# hmi.net
KiCad netlist of a schematic drawn in Altium Designer
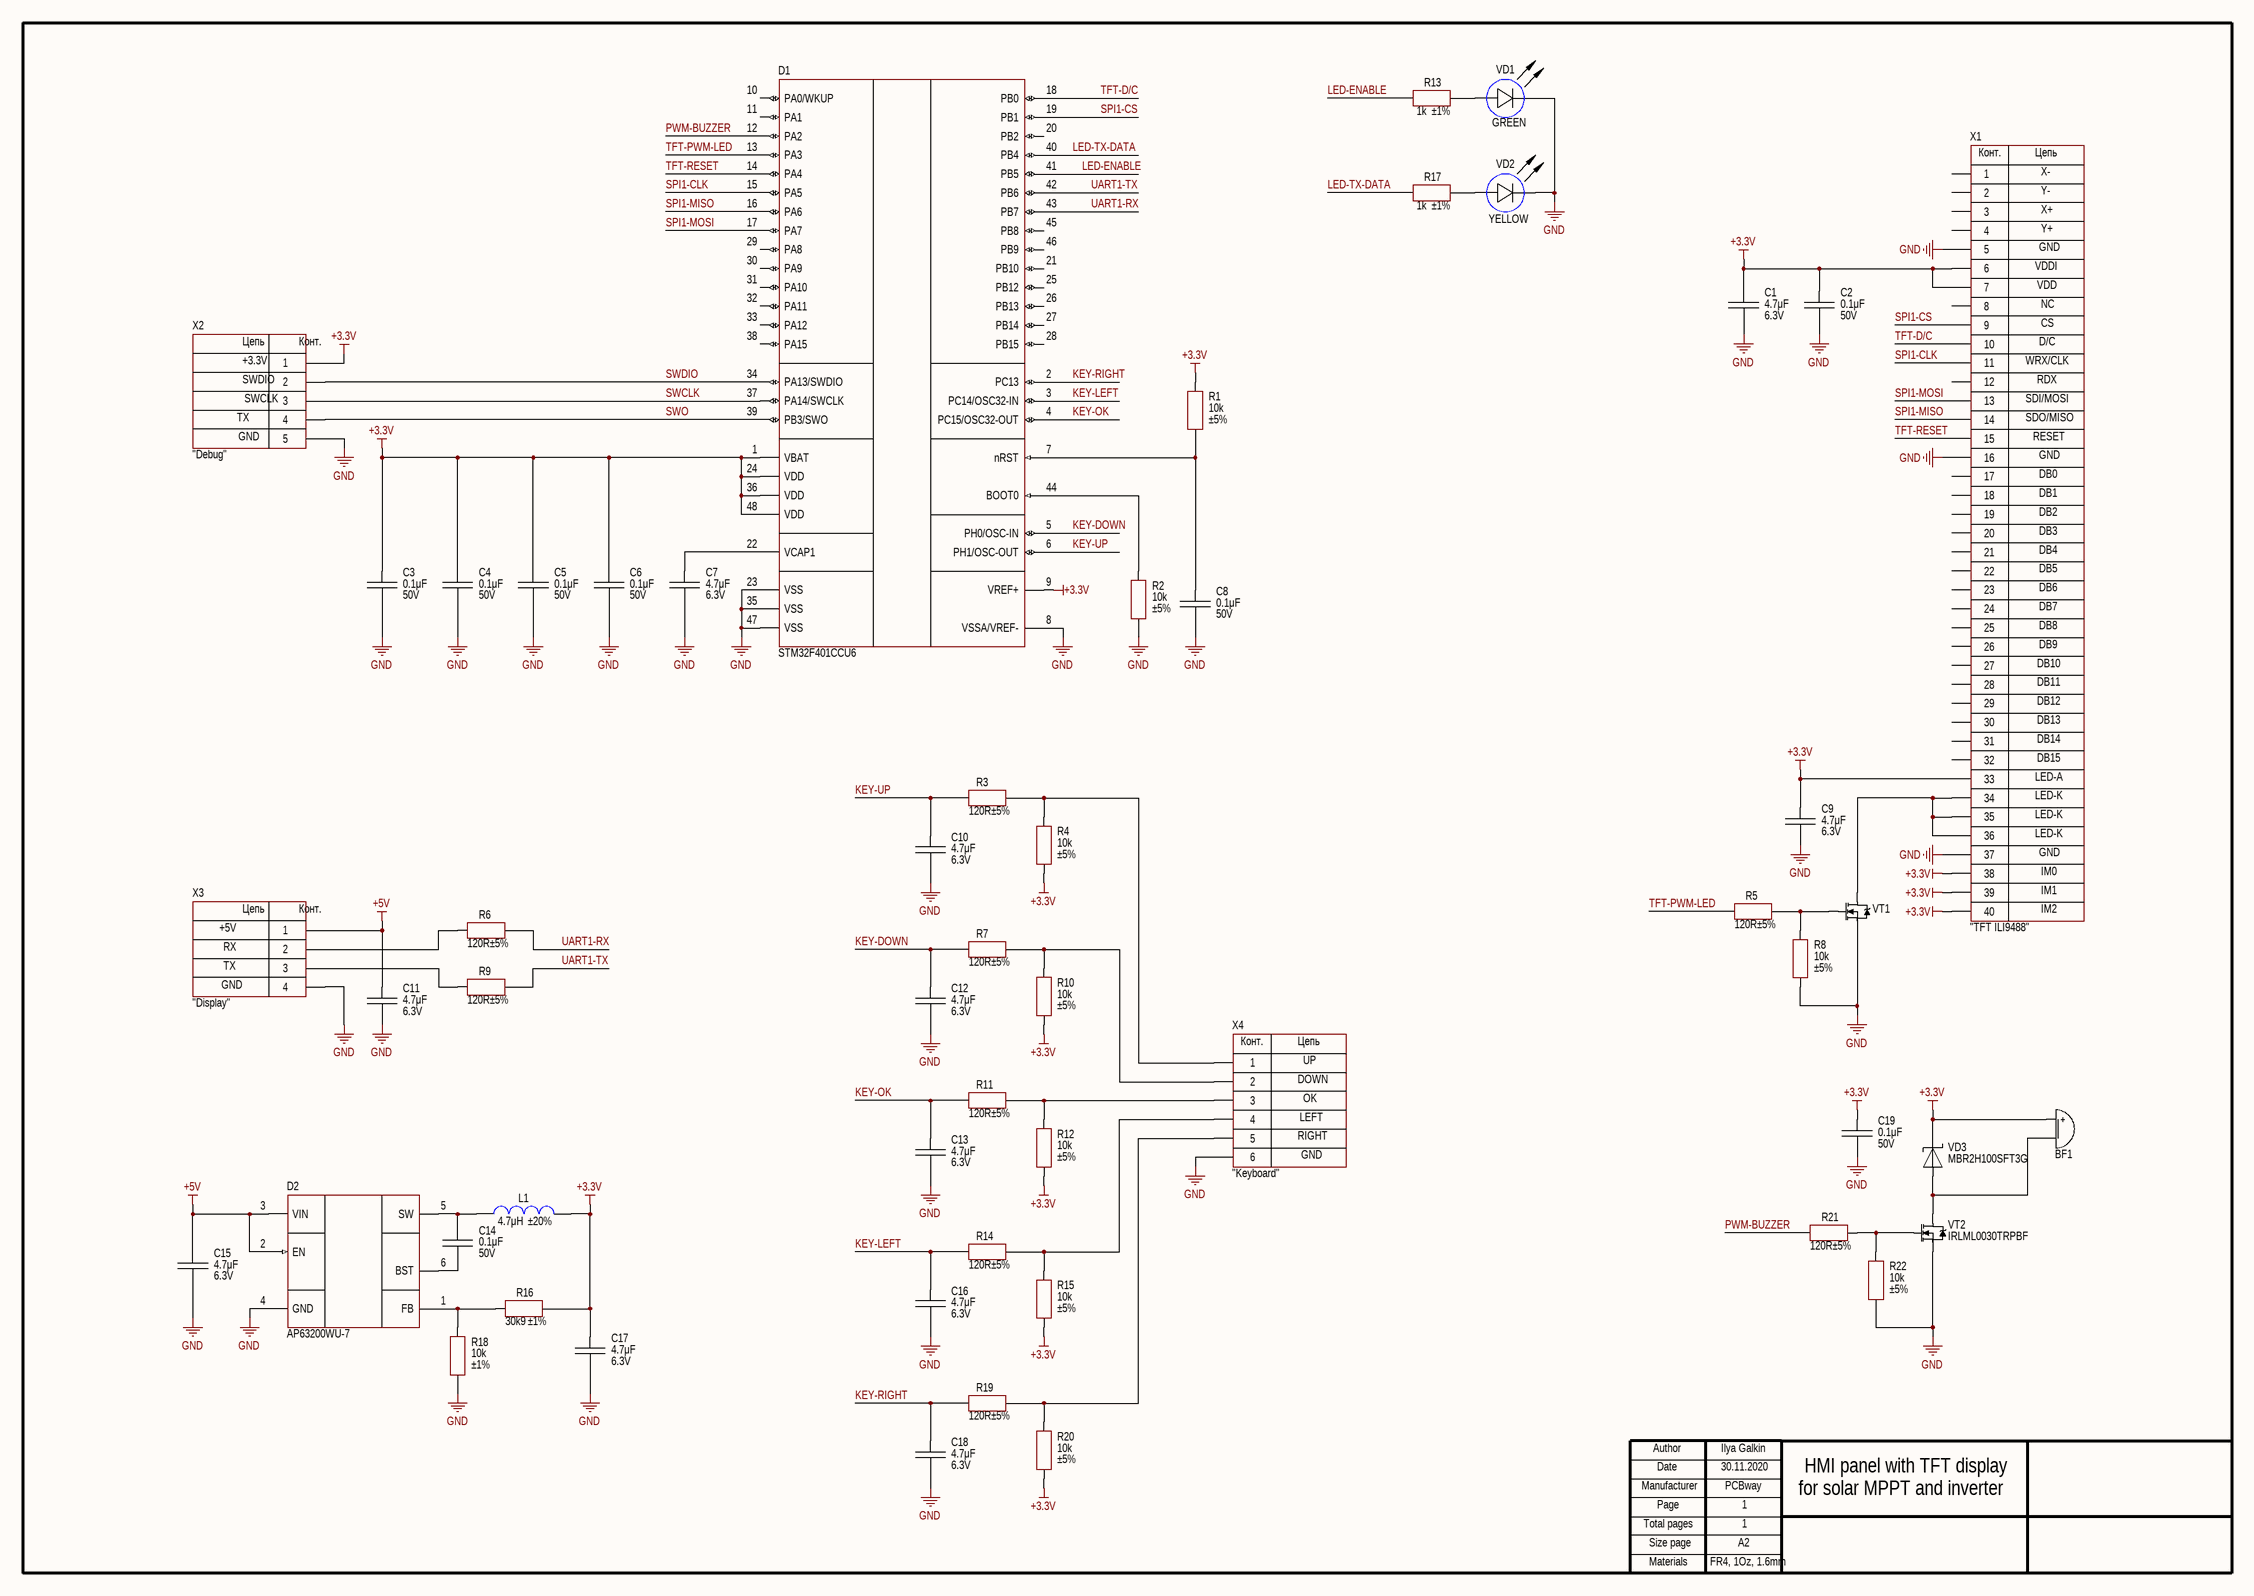
[diagram p0: hmi.SchDoc]

(export (version "E")
  (design (tool "Eeschema 10.0.6"))
  (components
    (comp (ref "BF1")
      (value "~")
      (footprint "BUZ: CMT-7525")
      (fields
        (field (name "MANUFACTURER") "Jiangsu")
        (field (name "VALUEMANUFACTURERPARTNUMBER") "SMD, 7.5x7.5x2.5 mm, 2.7 kHz, 3.6VDC, 80dB, -20...+70°C")
        (field (name "PARTNUMBER") "MLT-7525")
      )
      (libsource (lib "electromechanics") (part "Buzzer"))
    )
    (comp (ref "C1")
      (value "4.7μF")
      (footprint "CAP: 0603")
      (fields
        (field (name "MANUFACTURER") "Samsung")
        (field (name "PARTNUMBER") "CL10B475KQ8NQNC")
        (field (name "VALUEMANUFACTURERPARTNUMBER") "Ceramic capacitor, 4.7μF, X7R, ±10%, 6.3V, 0603, -55...+125°C")
        (field (name "VOLTAGE") "6.3V")
      )
      (libsource (lib "Capacitor") (part "Ceramic_0603"))
    )
    (comp (ref "C2")
      (value "0.1μF")
      (footprint "CAP: 0603")
      (fields
        (field (name "MANUFACTURER") "Samsung")
        (field (name "PARTNUMBER") "CL10B104KB8WPND")
        (field (name "VALUEMANUFACTURERPARTNUMBER") "Ceramic capacitor, 0.1μF, X7R, ±10%, 50V, 0603, -55...+125°C")
        (field (name "VOLTAGE") "50V")
      )
      (libsource (lib "Capacitor") (part "Ceramic_0603"))
    )
    (comp (ref "C3")
      (value "0.1μF")
      (footprint "CAP: 0603")
      (fields
        (field (name "MANUFACTURER") "Samsung")
        (field (name "PARTNUMBER") "CL10B104KB8WPND")
        (field (name "VALUEMANUFACTURERPARTNUMBER") "Ceramic capacitor, 0.1μF, X7R, ±10%, 50V, 0603, -55...+125°C")
        (field (name "VOLTAGE") "50V")
      )
      (libsource (lib "Capacitor") (part "Ceramic_0603"))
    )
    (comp (ref "C4")
      (value "0.1μF")
      (footprint "CAP: 0603")
      (fields
        (field (name "MANUFACTURER") "Samsung")
        (field (name "PARTNUMBER") "CL10B104KB8WPND")
        (field (name "VALUEMANUFACTURERPARTNUMBER") "Ceramic capacitor, 0.1μF, X7R, ±10%, 50V, 0603, -55...+125°C")
        (field (name "VOLTAGE") "50V")
      )
      (libsource (lib "Capacitor") (part "Ceramic_0603"))
    )
    (comp (ref "C5")
      (value "0.1μF")
      (footprint "CAP: 0603")
      (fields
        (field (name "MANUFACTURER") "Samsung")
        (field (name "PARTNUMBER") "CL10B104KB8WPND")
        (field (name "VALUEMANUFACTURERPARTNUMBER") "Ceramic capacitor, 0.1μF, X7R, ±10%, 50V, 0603, -55...+125°C")
        (field (name "VOLTAGE") "50V")
      )
      (libsource (lib "Capacitor") (part "Ceramic_0603"))
    )
    (comp (ref "C6")
      (value "0.1μF")
      (footprint "CAP: 0603")
      (fields
        (field (name "MANUFACTURER") "Samsung")
        (field (name "PARTNUMBER") "CL10B104KB8WPND")
        (field (name "VALUEMANUFACTURERPARTNUMBER") "Ceramic capacitor, 0.1μF, X7R, ±10%, 50V, 0603, -55...+125°C")
        (field (name "VOLTAGE") "50V")
      )
      (libsource (lib "Capacitor") (part "Ceramic_0603"))
    )
    (comp (ref "C7")
      (value "4.7μF")
      (footprint "CAP: 0603")
      (fields
        (field (name "MANUFACTURER") "Samsung")
        (field (name "PARTNUMBER") "CL10B475KQ8NQNC")
        (field (name "VALUEMANUFACTURERPARTNUMBER") "Ceramic capacitor, 4.7μF, X7R, ±10%, 6.3V, 0603, -55...+125°C")
        (field (name "VOLTAGE") "6.3V")
      )
      (libsource (lib "Capacitor") (part "Ceramic_0603"))
    )
    (comp (ref "C8")
      (value "0.1μF")
      (footprint "CAP: 0603")
      (fields
        (field (name "MANUFACTURER") "Samsung")
        (field (name "PARTNUMBER") "CL10B104KB8WPND")
        (field (name "VALUEMANUFACTURERPARTNUMBER") "Ceramic capacitor, 0.1μF, X7R, ±10%, 50V, 0603, -55...+125°C")
        (field (name "VOLTAGE") "50V")
      )
      (libsource (lib "Capacitor") (part "Ceramic_0603"))
    )
    (comp (ref "C9")
      (value "4.7μF")
      (footprint "CAP: 0603")
      (fields
        (field (name "MANUFACTURER") "Samsung")
        (field (name "PARTNUMBER") "CL10B475KQ8NQNC")
        (field (name "VALUEMANUFACTURERPARTNUMBER") "Ceramic capacitor, 4.7μF, X7R, ±10%, 6.3V, 0603, -55...+125°C")
        (field (name "VOLTAGE") "6.3V")
      )
      (libsource (lib "Capacitor") (part "Ceramic_0603"))
    )
    (comp (ref "C10")
      (value "4.7μF")
      (footprint "CAP: 0603")
      (fields
        (field (name "MANUFACTURER") "Samsung")
        (field (name "PARTNUMBER") "CL10B475KQ8NQNC")
        (field (name "VALUEMANUFACTURERPARTNUMBER") "Ceramic capacitor, 4.7μF, X7R, ±10%, 6.3V, 0603, -55...+125°C")
        (field (name "VOLTAGE") "6.3V")
      )
      (libsource (lib "Capacitor") (part "Ceramic_0603"))
    )
    (comp (ref "C11")
      (value "4.7μF")
      (footprint "CAP: 0603")
      (fields
        (field (name "MANUFACTURER") "Samsung")
        (field (name "PARTNUMBER") "CL10B475KQ8NQNC")
        (field (name "VALUEMANUFACTURERPARTNUMBER") "Ceramic capacitor, 4.7μF, X7R, ±10%, 6.3V, 0603, -55...+125°C")
        (field (name "VOLTAGE") "6.3V")
      )
      (libsource (lib "Capacitor") (part "Ceramic_0603"))
    )
    (comp (ref "C12")
      (value "4.7μF")
      (footprint "CAP: 0603")
      (fields
        (field (name "MANUFACTURER") "Samsung")
        (field (name "PARTNUMBER") "CL10B475KQ8NQNC")
        (field (name "VALUEMANUFACTURERPARTNUMBER") "Ceramic capacitor, 4.7μF, X7R, ±10%, 6.3V, 0603, -55...+125°C")
        (field (name "VOLTAGE") "6.3V")
      )
      (libsource (lib "Capacitor") (part "Ceramic_0603"))
    )
    (comp (ref "C13")
      (value "4.7μF")
      (footprint "CAP: 0603")
      (fields
        (field (name "MANUFACTURER") "Samsung")
        (field (name "PARTNUMBER") "CL10B475KQ8NQNC")
        (field (name "VALUEMANUFACTURERPARTNUMBER") "Ceramic capacitor, 4.7μF, X7R, ±10%, 6.3V, 0603, -55...+125°C")
        (field (name "VOLTAGE") "6.3V")
      )
      (libsource (lib "Capacitor") (part "Ceramic_0603"))
    )
    (comp (ref "C14")
      (value "0.1μF")
      (footprint "CAP: 0603")
      (fields
        (field (name "MANUFACTURER") "Samsung")
        (field (name "PARTNUMBER") "CL10B104KB8WPND")
        (field (name "VALUEMANUFACTURERPARTNUMBER") "Ceramic capacitor, 0.1μF, X7R, ±10%, 50V, 0603, -55...+125°C")
        (field (name "VOLTAGE") "50V")
      )
      (libsource (lib "Capacitor") (part "Ceramic_0603"))
    )
    (comp (ref "C15")
      (value "4.7μF")
      (footprint "CAP: 0603")
      (fields
        (field (name "MANUFACTURER") "Samsung")
        (field (name "PARTNUMBER") "CL10B475KQ8NQNC")
        (field (name "VALUEMANUFACTURERPARTNUMBER") "Ceramic capacitor, 4.7μF, X7R, ±10%, 6.3V, 0603, -55...+125°C")
        (field (name "VOLTAGE") "6.3V")
      )
      (libsource (lib "Capacitor") (part "Ceramic_0603"))
    )
    (comp (ref "C16")
      (value "4.7μF")
      (footprint "CAP: 0603")
      (fields
        (field (name "MANUFACTURER") "Samsung")
        (field (name "PARTNUMBER") "CL10B475KQ8NQNC")
        (field (name "VALUEMANUFACTURERPARTNUMBER") "Ceramic capacitor, 4.7μF, X7R, ±10%, 6.3V, 0603, -55...+125°C")
        (field (name "VOLTAGE") "6.3V")
      )
      (libsource (lib "Capacitor") (part "Ceramic_0603"))
    )
    (comp (ref "C17")
      (value "4.7μF")
      (footprint "CAP: 0603")
      (fields
        (field (name "MANUFACTURER") "Samsung")
        (field (name "PARTNUMBER") "CL10B475KQ8NQNC")
        (field (name "VALUEMANUFACTURERPARTNUMBER") "Ceramic capacitor, 4.7μF, X7R, ±10%, 6.3V, 0603, -55...+125°C")
        (field (name "VOLTAGE") "6.3V")
      )
      (libsource (lib "Capacitor") (part "Ceramic_0603"))
    )
    (comp (ref "C18")
      (value "4.7μF")
      (footprint "CAP: 0603")
      (fields
        (field (name "MANUFACTURER") "Samsung")
        (field (name "PARTNUMBER") "CL10B475KQ8NQNC")
        (field (name "VALUEMANUFACTURERPARTNUMBER") "Ceramic capacitor, 4.7μF, X7R, ±10%, 6.3V, 0603, -55...+125°C")
        (field (name "VOLTAGE") "6.3V")
      )
      (libsource (lib "Capacitor") (part "Ceramic_0603"))
    )
    (comp (ref "C19")
      (value "0.1μF")
      (footprint "CAP: 0603")
      (fields
        (field (name "MANUFACTURER") "Samsung")
        (field (name "PARTNUMBER") "CL10B104KB8WPND")
        (field (name "VALUEMANUFACTURERPARTNUMBER") "Ceramic capacitor, 0.1μF, X7R, ±10%, 50V, 0603, -55...+125°C")
        (field (name "VOLTAGE") "50V")
      )
      (libsource (lib "Capacitor") (part "Ceramic_0603"))
    )
    (comp (ref "D1")
      (value "~")
      (footprint "48-QFN (7x7)")
      (description "Cortex-M4")
      (fields (field (name "MANUFACTURER") "STMicroelectronics") (field (name "PARTNUMBER") "STM32F401CCU6"))
      (libsource (lib "ic-mcu") (part "STM32F401CCU6"))
    )
    (comp (ref "D2")
      (value "~")
      (footprint "SOT23-6")
      (description "Buck converter")
      (fields
        (field (name "MANUFACTURER") "Diodes")
        (field (name "VALUEMANUFACTURERPARTNUMBER") "DC/DC buck converter, input 3.8...32V, 500kHz, output 1.2...12V, 2A, -40...+85°C, SOT23-6")
        (field (name "PARTNUMBER") "AP63200WU-7")
      )
      (libsource (lib "ic-power-supply") (part "AP63200WU-7"))
    )
    (comp (ref "L1")
      (value "4.7μH")
      (footprint "IND: CD32")
      (fields
        (field (name "MANUFACTURER") "YJYCOIN")
        (field (name "PARTNUMBER") "CD32YP0302-4R7M")
        (field (name "VALUEMANUFACTURERPARTNUMBER") "Fixed inductor, 4.7μH, ±20%, CD32 series, 1.5A, -40...+125°C")
        (field (name "TOLERANCE") "±20%")
      )
      (libsource (lib "inductor") (part "Inductor_CD32"))
    )
    (comp (ref "R1")
      (value "10k")
      (footprint "RES: 0603")
      (fields
        (field (name "MANUFACTURER") "Yageo")
        (field (name "PARTNUMBER") "RC0603JR-0710KL")
        (field (name "VALUEMANUFACTURERPARTNUMBER") "Resistor film, 10k, ±5%, 0603, 0.1W, -55...+125°C")
        (field (name "TOLERANCE") "±5%")
      )
      (libsource (lib "") (part "Resistor_0603_2"))
    )
    (comp (ref "R2")
      (value "10k")
      (footprint "RES: 0603")
      (fields
        (field (name "MANUFACTURER") "Yageo")
        (field (name "PARTNUMBER") "RC0603JR-0710KL")
        (field (name "VALUEMANUFACTURERPARTNUMBER") "Resistor film, 10k, ±5%, 0603, 0.1W, -55...+125°C")
        (field (name "TOLERANCE") "±5%")
      )
      (libsource (lib "") (part "Resistor_0603_2"))
    )
    (comp (ref "R3")
      (value "120R")
      (footprint "RES: 0603")
      (fields
        (field (name "MANUFACTURER") "Yageo")
        (field (name "PARTNUMBER") "RC0603JR-07120RL")
        (field (name "VALUEMANUFACTURERPARTNUMBER") "Resistor film, 120R, ±5%, 0603, 0.1W, -55...+125°C")
        (field (name "TOLERANCE") "±5%")
      )
      (libsource (lib "resistor") (part "Resistor_0603"))
    )
    (comp (ref "R4")
      (value "10k")
      (footprint "RES: 0603")
      (fields
        (field (name "MANUFACTURER") "Yageo")
        (field (name "PARTNUMBER") "RC0603JR-0710KL")
        (field (name "VALUEMANUFACTURERPARTNUMBER") "Resistor film, 10k, ±5%, 0603, 0.1W, -55...+125°C")
        (field (name "TOLERANCE") "±5%")
      )
      (libsource (lib "") (part "Resistor_0603_2"))
    )
    (comp (ref "R5")
      (value "120R")
      (footprint "RES: 0603")
      (fields
        (field (name "MANUFACTURER") "Yageo")
        (field (name "PARTNUMBER") "RC0603JR-07120RL")
        (field (name "VALUEMANUFACTURERPARTNUMBER") "Resistor film, 120R, ±5%, 0603, 0.1W, -55...+125°C")
        (field (name "TOLERANCE") "±5%")
      )
      (libsource (lib "") (part "Resistor_0603_1"))
    )
    (comp (ref "R6")
      (value "120R")
      (footprint "RES: 0603")
      (fields
        (field (name "MANUFACTURER") "Yageo")
        (field (name "PARTNUMBER") "RC0603JR-07120RL")
        (field (name "VALUEMANUFACTURERPARTNUMBER") "Resistor film, 120R, ±5%, 0603, 0.1W, -55...+125°C")
        (field (name "TOLERANCE") "±5%")
      )
      (libsource (lib "") (part "Resistor_0603_1"))
    )
    (comp (ref "R7")
      (value "120R")
      (footprint "RES: 0603")
      (fields
        (field (name "MANUFACTURER") "Yageo")
        (field (name "PARTNUMBER") "RC0603JR-07120RL")
        (field (name "VALUEMANUFACTURERPARTNUMBER") "Resistor film, 120R, ±5%, 0603, 0.1W, -55...+125°C")
        (field (name "TOLERANCE") "±5%")
      )
      (libsource (lib "resistor") (part "Resistor_0603"))
    )
    (comp (ref "R8")
      (value "10k")
      (footprint "RES: 0603")
      (fields
        (field (name "MANUFACTURER") "Yageo")
        (field (name "PARTNUMBER") "RC0603JR-0710KL")
        (field (name "VALUEMANUFACTURERPARTNUMBER") "Resistor film, 10k, ±5%, 0603, 0.1W, -55...+125°C")
        (field (name "TOLERANCE") "±5%")
      )
      (libsource (lib "") (part "Resistor_0603_2"))
    )
    (comp (ref "R9")
      (value "120R")
      (footprint "RES: 0603")
      (fields
        (field (name "MANUFACTURER") "Yageo")
        (field (name "PARTNUMBER") "RC0603JR-07120RL")
        (field (name "VALUEMANUFACTURERPARTNUMBER") "Resistor film, 120R, ±5%, 0603, 0.1W, -55...+125°C")
        (field (name "TOLERANCE") "±5%")
      )
      (libsource (lib "") (part "Resistor_0603_1"))
    )
    (comp (ref "R10")
      (value "10k")
      (footprint "RES: 0603")
      (fields
        (field (name "MANUFACTURER") "Yageo")
        (field (name "PARTNUMBER") "RC0603JR-0710KL")
        (field (name "VALUEMANUFACTURERPARTNUMBER") "Resistor film, 10k, ±5%, 0603, 0.1W, -55...+125°C")
        (field (name "TOLERANCE") "±5%")
      )
      (libsource (lib "") (part "Resistor_0603_2"))
    )
    (comp (ref "R11")
      (value "120R")
      (footprint "RES: 0603")
      (fields
        (field (name "MANUFACTURER") "Yageo")
        (field (name "PARTNUMBER") "RC0603JR-07120RL")
        (field (name "VALUEMANUFACTURERPARTNUMBER") "Resistor film, 120R, ±5%, 0603, 0.1W, -55...+125°C")
        (field (name "TOLERANCE") "±5%")
      )
      (libsource (lib "resistor") (part "Resistor_0603"))
    )
    (comp (ref "R12")
      (value "10k")
      (footprint "RES: 0603")
      (fields
        (field (name "MANUFACTURER") "Yageo")
        (field (name "PARTNUMBER") "RC0603JR-0710KL")
        (field (name "VALUEMANUFACTURERPARTNUMBER") "Resistor film, 10k, ±5%, 0603, 0.1W, -55...+125°C")
        (field (name "TOLERANCE") "±5%")
      )
      (libsource (lib "") (part "Resistor_0603_2"))
    )
    (comp (ref "R13")
      (value "1k")
      (footprint "RES: 0603")
      (fields
        (field (name "MANUFACTURER") "Yageo")
        (field (name "PARTNUMBER") "RC0603JR-071KL")
        (field (name "VALUEMANUFACTURERPARTNUMBER") "Resistor film, 1k, ±1%, 0603, 0.1W, -55...+125°C")
        (field (name "TOLERANCE") "±1%")
      )
      (libsource (lib "Resistor") (part "Resistor_0603"))
    )
    (comp (ref "R14")
      (value "120R")
      (footprint "RES: 0603")
      (fields
        (field (name "MANUFACTURER") "Yageo")
        (field (name "PARTNUMBER") "RC0603JR-07120RL")
        (field (name "VALUEMANUFACTURERPARTNUMBER") "Resistor film, 120R, ±5%, 0603, 0.1W, -55...+125°C")
        (field (name "TOLERANCE") "±5%")
      )
      (libsource (lib "resistor") (part "Resistor_0603"))
    )
    (comp (ref "R15")
      (value "10k")
      (footprint "RES: 0603")
      (fields
        (field (name "MANUFACTURER") "Yageo")
        (field (name "PARTNUMBER") "RC0603JR-0710KL")
        (field (name "VALUEMANUFACTURERPARTNUMBER") "Resistor film, 10k, ±5%, 0603, 0.1W, -55...+125°C")
        (field (name "TOLERANCE") "±5%")
      )
      (libsource (lib "") (part "Resistor_0603_2"))
    )
    (comp (ref "R16")
      (value "30k9")
      (footprint "RES: 0603")
      (fields
        (field (name "MANUFACTURER") "Yageo")
        (field (name "PARTNUMBER") "RC0603FR-0730K9L")
        (field (name "VALUEMANUFACTURERPARTNUMBER") "Resistor film, 30k9, ±1%, 0603, 0.1W, -55...+125°C")
        (field (name "TOLERANCE") "±1%")
      )
      (libsource (lib "Resistor") (part "Resistor_0603"))
    )
    (comp (ref "R17")
      (value "1k")
      (footprint "RES: 0603")
      (fields
        (field (name "MANUFACTURER") "Yageo")
        (field (name "PARTNUMBER") "RC0603JR-071KL")
        (field (name "VALUEMANUFACTURERPARTNUMBER") "Resistor film, 1k, ±1%, 0603, 0.1W, -55...+125°C")
        (field (name "TOLERANCE") "±1%")
      )
      (libsource (lib "Resistor") (part "Resistor_0603"))
    )
    (comp (ref "R18")
      (value "10k")
      (footprint "RES: 0603")
      (fields
        (field (name "MANUFACTURER") "Yageo")
        (field (name "PARTNUMBER") "AC0603FR-0710KL")
        (field (name "VALUEMANUFACTURERPARTNUMBER") "Resistor film, 10k, ±1%, 0603, 0.1W, -55...+125°C")
        (field (name "TOLERANCE") "±1%")
      )
      (libsource (lib "") (part "Resistor_0603_2"))
    )
    (comp (ref "R19")
      (value "120R")
      (footprint "RES: 0603")
      (fields
        (field (name "MANUFACTURER") "Yageo")
        (field (name "PARTNUMBER") "RC0603JR-07120RL")
        (field (name "VALUEMANUFACTURERPARTNUMBER") "Resistor film, 120R, ±5%, 0603, 0.1W, -55...+125°C")
        (field (name "TOLERANCE") "±5%")
      )
      (libsource (lib "resistor") (part "Resistor_0603"))
    )
    (comp (ref "R20")
      (value "10k")
      (footprint "RES: 0603")
      (fields
        (field (name "MANUFACTURER") "Yageo")
        (field (name "PARTNUMBER") "RC0603JR-0710KL")
        (field (name "VALUEMANUFACTURERPARTNUMBER") "Resistor film, 10k, ±5%, 0603, 0.1W, -55...+125°C")
        (field (name "TOLERANCE") "±5%")
      )
      (libsource (lib "") (part "Resistor_0603_2"))
    )
    (comp (ref "R21")
      (value "120R")
      (footprint "RES: 0603")
      (fields
        (field (name "MANUFACTURER") "Yageo")
        (field (name "PARTNUMBER") "RC0603JR-07120RL")
        (field (name "VALUEMANUFACTURERPARTNUMBER") "Resistor film, 120R, ±5%, 0603, 0.1W, -55...+125°C")
        (field (name "TOLERANCE") "±5%")
      )
      (libsource (lib "") (part "Resistor_0603_1"))
    )
    (comp (ref "R22")
      (value "10k")
      (footprint "RES: 0603")
      (fields
        (field (name "MANUFACTURER") "Yageo")
        (field (name "PARTNUMBER") "RC0603JR-0710KL")
        (field (name "VALUEMANUFACTURERPARTNUMBER") "Resistor film, 10k, ±5%, 0603, 0.1W, -55...+125°C")
        (field (name "TOLERANCE") "±5%")
      )
      (libsource (lib "") (part "Resistor_0603_2"))
    )
    (comp (ref "VD1")
      (value "~")
      (footprint "LED: 0603G")
      (fields
        (field (name "MANUFACTURER") "Wurth")
        (field (name "VALUEMANUFACTURERPARTNUMBER") "LED, 20mA, 2V, 0603, -55...+150°C")
        (field (name "PARTNUMBER") "150060VS75000")
        (field (name "COLOR") "GREEN")
      )
      (libsource (lib "Diode") (part "LED_single"))
    )
    (comp (ref "VD2")
      (value "~")
      (footprint "LED: 0603Y")
      (fields
        (field (name "MANUFACTURER") "Wurth")
        (field (name "VALUEMANUFACTURERPARTNUMBER") "LED, 20mA, 2V, 0603, -55...+150°C")
        (field (name "PARTNUMBER") "150060YS75000")
        (field (name "COLOR") "YELLOW")
      )
      (libsource (lib "Diode") (part "LED_single"))
    )
    (comp (ref "VD3")
      (value "~")
      (footprint "DIODE: SOD123F")
      (fields
        (field (name "MANUFACTURER") "ON Semiconductor")
        (field (name "VALUEMANUFACTURERPARTNUMBER") "Schottky diode, 100V, 2A, 840mV, 15pF, SOD-123F, -55...+150°C")
        (field (name "VOLTAGE") "100V")
        (field (name "PARTNUMBER") "MBR2H100SFT3G")
      )
      (libsource (lib "Diode") (part "Schottky_single"))
    )
    (comp (ref "VT1")
      (value "~")
      (footprint "SOT23")
      (fields
        (field (name "MANUFACTURER") "Infineon Technologies")
        (field (name "VALUEMANUFACTURERPARTNUMBER") "MOSFET N-channel transistor, 30V, 5.3A, 2.6nC, 1.3W, 27mOhm, 382pF, SOT-23, -55...+150°C")
        (field (name "PARTNUMBER") "IRLML0030TRPBF")
      )
      (libsource (lib "transistor") (part "MOSFET_N_132"))
    )
    (comp (ref "VT2")
      (value "~")
      (footprint "SOT23")
      (fields
        (field (name "MANUFACTURER") "Infineon Technologies")
        (field (name "VALUEMANUFACTURERPARTNUMBER") "MOSFET N-channel transistor, 30V, 5.3A, 2.6nC, 1.3W, 27mOhm, 382pF, SOT-23, -55...+150°C")
        (field (name "PARTNUMBER") "IRLML0030TRPBF")
      )
      (libsource (lib "transistor") (part "MOSFET_N_132"))
    )
    (comp (ref "X1")
      (value "~")
      (footprint "CON: FFC/FPC-40-0.5")
      (fields
        (field (name "MANUFACTURER") "JUSHUO")
        (field (name "VALUEMANUFACTURERPARTNUMBER") "Connector, 40pin, 0.5mm, FFC/FPC, Top contact")
        (field (name "PARTNUMBER") "AFC07-S40ECC-00")
        (field (name "COMMENTTEXT") "\"TFT ILI9488\"")
      )
      (libsource (lib "connector") (part "Connector_FFC_40"))
    )
    (comp (ref "X2")
      (value "~")
      (footprint "CON: PLS-5")
      (fields
        (field (name "MANUFACTURER") "Connfly")
        (field (name "VALUEMANUFACTURERPARTNUMBER") "Connector, 5pin, 2.54mm, 500VAC, 3A")
        (field (name "PARTNUMBER") "PLS-5")
        (field (name "COMMENTTEXT") "\"Debug\"")
      )
      (libsource (lib "connector") (part "PLS-5"))
    )
    (comp (ref "X3")
      (value "~")
      (footprint "CON: CWF-4R")
      (fields
        (field (name "MANUFACTURER") "Connfly")
        (field (name "VALUEMANUFACTURERPARTNUMBER") "Connector, 4pin, 2.54mm, 250VAC, 3A")
        (field (name "PARTNUMBER") "CWF-4R")
        (field (name "COMMENTTEXT") "\"Display\"")
      )
      (libsource (lib "connector") (part "CWF-4"))
    )
    (comp (ref "X4")
      (value "~")
      (footprint "CON: CWF-6R")
      (fields
        (field (name "MANUFACTURER") "Connfly")
        (field (name "VALUEMANUFACTURERPARTNUMBER") "Connector, 6pin, 2.54mm, 250VAC, 3A")
        (field (name "PARTNUMBER") "CWF-6R")
        (field (name "COMMENTTEXT") "\"Keyboard\"")
      )
      (libsource (lib "connector") (part "CWF-6"))
    )
  )
  (nets
    (net (code "1") (name "+3.3V") (class "Default")
      (node (ref "BF1") (pin "1") (pinfunction "+_1") (pintype "passive"))
      (node (ref "C1") (pin "2") (pinfunction "2_2") (pintype "power_in"))
      (node (ref "C17") (pin "2") (pinfunction "2_2") (pintype "power_in"))
      (node (ref "C19") (pin "2") (pinfunction "2_2") (pintype "power_in"))
      (node (ref "C2") (pin "2") (pinfunction "2_2") (pintype "power_in"))
      (node (ref "C3") (pin "2") (pinfunction "2_2") (pintype "power_in"))
      (node (ref "C4") (pin "2") (pinfunction "2_2") (pintype "power_in"))
      (node (ref "C5") (pin "2") (pinfunction "2_2") (pintype "power_in"))
      (node (ref "C6") (pin "2") (pinfunction "2_2") (pintype "power_in"))
      (node (ref "C9") (pin "2") (pinfunction "2_2") (pintype "power_in"))
      (node (ref "D1") (pin "1") (pinfunction "VBAT_1") (pintype "passive"))
      (node (ref "D1") (pin "24") (pinfunction "VDD_24") (pintype "passive"))
      (node (ref "D1") (pin "36") (pinfunction "VDD_36") (pintype "passive"))
      (node (ref "D1") (pin "48") (pinfunction "VDD_48") (pintype "passive"))
      (node (ref "D1") (pin "9") (pinfunction "VREF+_9") (pintype "passive"))
      (node (ref "L1") (pin "1") (pinfunction "1_1") (pintype "passive"))
      (node (ref "R1") (pin "2") (pinfunction "2_2") (pintype "passive"))
      (node (ref "R10") (pin "1") (pinfunction "1_1") (pintype "passive"))
      (node (ref "R12") (pin "1") (pinfunction "1_1") (pintype "passive"))
      (node (ref "R15") (pin "1") (pinfunction "1_1") (pintype "passive"))
      (node (ref "R16") (pin "1") (pinfunction "1_1") (pintype "passive"))
      (node (ref "R20") (pin "1") (pinfunction "1_1") (pintype "passive"))
      (node (ref "R4") (pin "1") (pinfunction "1_1") (pintype "passive"))
      (node (ref "VD3") (pin "2") (pinfunction "2_2") (pintype "passive"))
      (node (ref "X1") (pin "33") (pinfunction "33_33") (pintype "passive"))
      (node (ref "X1") (pin "38") (pinfunction "38_38") (pintype "passive"))
      (node (ref "X1") (pin "39") (pinfunction "39_39") (pintype "passive"))
      (node (ref "X1") (pin "40") (pinfunction "40_40") (pintype "passive"))
      (node (ref "X1") (pin "6") (pinfunction "6_6") (pintype "passive"))
      (node (ref "X1") (pin "7") (pinfunction "7_7") (pintype "passive"))
      (node (ref "X2") (pin "1") (pinfunction "1_1") (pintype "passive"))
    )
    (net (code "2") (name "+5V") (class "Default")
      (node (ref "C11") (pin "2") (pinfunction "2_2") (pintype "power_in"))
      (node (ref "C15") (pin "2") (pinfunction "2_2") (pintype "power_in"))
      (node (ref "D2") (pin "2") (pinfunction "EN_2") (pintype "input"))
      (node (ref "D2") (pin "3") (pinfunction "VIN_3") (pintype "passive"))
      (node (ref "X3") (pin "1") (pinfunction "1_1") (pintype "passive"))
    )
    (net (code "3") (name "/KEY-DOWN") (class "Default")
      (node (ref "C12") (pin "2") (pinfunction "2_2") (pintype "power_in"))
      (node (ref "D1") (pin "5") (pinfunction "PH0/OSC-IN_5") (pintype "bidirectional"))
      (node (ref "R7") (pin "1") (pinfunction "1_1") (pintype "passive"))
    )
    (net (code "4") (name "/KEY-LEFT") (class "Default")
      (node (ref "C16") (pin "2") (pinfunction "2_2") (pintype "power_in"))
      (node (ref "D1") (pin "3") (pinfunction "PC14/OSC32-IN_3") (pintype "bidirectional"))
      (node (ref "R14") (pin "1") (pinfunction "1_1") (pintype "passive"))
    )
    (net (code "5") (name "/KEY-OK") (class "Default")
      (node (ref "C13") (pin "2") (pinfunction "2_2") (pintype "power_in"))
      (node (ref "D1") (pin "4") (pinfunction "PC15/OSC32-OUT_4") (pintype "bidirectional"))
      (node (ref "R11") (pin "1") (pinfunction "1_1") (pintype "passive"))
    )
    (net (code "6") (name "/KEY-RIGHT") (class "Default")
      (node (ref "C18") (pin "2") (pinfunction "2_2") (pintype "power_in"))
      (node (ref "D1") (pin "2") (pinfunction "PC13_2") (pintype "bidirectional"))
      (node (ref "R19") (pin "1") (pinfunction "1_1") (pintype "passive"))
    )
    (net (code "7") (name "/KEY-UP") (class "Default")
      (node (ref "C10") (pin "2") (pinfunction "2_2") (pintype "power_in"))
      (node (ref "D1") (pin "6") (pinfunction "PH1/OSC-OUT_6") (pintype "bidirectional"))
      (node (ref "R3") (pin "1") (pinfunction "1_1") (pintype "passive"))
    )
    (net (code "8") (name "/LED-ENABLE") (class "Default")
      (node (ref "D1") (pin "41") (pinfunction "PB5_41") (pintype "bidirectional"))
      (node (ref "R13") (pin "2") (pinfunction "2_2") (pintype "passive"))
    )
    (net (code "9") (name "/LED-TX-DATA") (class "Default")
      (node (ref "D1") (pin "40") (pinfunction "PB4_40") (pintype "bidirectional"))
      (node (ref "R17") (pin "2") (pinfunction "2_2") (pintype "passive"))
    )
    (net (code "10") (name "/PWM-BUZZER") (class "Default")
      (node (ref "D1") (pin "12") (pinfunction "PA2_12") (pintype "bidirectional"))
      (node (ref "R21") (pin "1") (pinfunction "1_1") (pintype "passive"))
    )
    (net (code "11") (name "/SPI1-CLK") (class "Default")
      (node (ref "D1") (pin "15") (pinfunction "PA5_15") (pintype "bidirectional"))
      (node (ref "X1") (pin "11") (pinfunction "11_11") (pintype "passive"))
    )
    (net (code "12") (name "/SPI1-CS") (class "Default")
      (node (ref "D1") (pin "19") (pinfunction "PB1_19") (pintype "bidirectional"))
      (node (ref "X1") (pin "9") (pinfunction "9_9") (pintype "passive"))
    )
    (net (code "13") (name "/SPI1-MISO") (class "Default")
      (node (ref "D1") (pin "16") (pinfunction "PA6_16") (pintype "bidirectional"))
      (node (ref "X1") (pin "14") (pinfunction "14_14") (pintype "passive"))
    )
    (net (code "14") (name "/SPI1-MOSI") (class "Default")
      (node (ref "D1") (pin "17") (pinfunction "PA7_17") (pintype "bidirectional"))
      (node (ref "X1") (pin "13") (pinfunction "13_13") (pintype "passive"))
    )
    (net (code "15") (name "/SWCLK") (class "Default")
      (node (ref "D1") (pin "37") (pinfunction "PA14/SWCLK_37") (pintype "bidirectional"))
      (node (ref "X2") (pin "3") (pinfunction "3_3") (pintype "power_in"))
    )
    (net (code "16") (name "/SWDIO") (class "Default")
      (node (ref "D1") (pin "34") (pinfunction "PA13/SWDIO_34") (pintype "bidirectional"))
      (node (ref "X2") (pin "2") (pinfunction "2_2") (pintype "passive"))
    )
    (net (code "17") (name "/SWO") (class "Default")
      (node (ref "D1") (pin "39") (pinfunction "PB3/SWO_39") (pintype "bidirectional"))
      (node (ref "X2") (pin "4") (pinfunction "4_4") (pintype "power_in"))
    )
    (net (code "18") (name "/TFT-D{slash}C") (class "Default")
      (node (ref "D1") (pin "18") (pinfunction "PB0_18") (pintype "bidirectional"))
      (node (ref "X1") (pin "10") (pinfunction "10_10") (pintype "passive"))
    )
    (net (code "19") (name "/TFT-PWM-LED") (class "Default")
      (node (ref "D1") (pin "13") (pinfunction "PA3_13") (pintype "bidirectional"))
      (node (ref "R5") (pin "1") (pinfunction "1_1") (pintype "passive"))
    )
    (net (code "20") (name "/TFT-RESET") (class "Default")
      (node (ref "D1") (pin "14") (pinfunction "PA4_14") (pintype "bidirectional"))
      (node (ref "X1") (pin "15") (pinfunction "15_15") (pintype "passive"))
    )
    (net (code "21") (name "/UART1-RX") (class "Default")
      (node (ref "D1") (pin "43") (pinfunction "PB7_43") (pintype "bidirectional"))
      (node (ref "R6") (pin "2") (pinfunction "2_2") (pintype "passive"))
    )
    (net (code "22") (name "/UART1-TX") (class "Default")
      (node (ref "D1") (pin "42") (pinfunction "PB6_42") (pintype "bidirectional"))
      (node (ref "R9") (pin "2") (pinfunction "2_2") (pintype "passive"))
    )
    (net (code "23") (name "GND") (class "Default")
      (node (ref "C1") (pin "1") (pinfunction "1_1") (pintype "power_in"))
      (node (ref "C10") (pin "1") (pinfunction "1_1") (pintype "power_in"))
      (node (ref "C11") (pin "1") (pinfunction "1_1") (pintype "power_in"))
      (node (ref "C12") (pin "1") (pinfunction "1_1") (pintype "power_in"))
      (node (ref "C13") (pin "1") (pinfunction "1_1") (pintype "power_in"))
      (node (ref "C15") (pin "1") (pinfunction "1_1") (pintype "power_in"))
      (node (ref "C16") (pin "1") (pinfunction "1_1") (pintype "power_in"))
      (node (ref "C17") (pin "1") (pinfunction "1_1") (pintype "power_in"))
      (node (ref "C18") (pin "1") (pinfunction "1_1") (pintype "power_in"))
      (node (ref "C19") (pin "1") (pinfunction "1_1") (pintype "power_in"))
      (node (ref "C2") (pin "1") (pinfunction "1_1") (pintype "power_in"))
      (node (ref "C3") (pin "1") (pinfunction "1_1") (pintype "power_in"))
      (node (ref "C4") (pin "1") (pinfunction "1_1") (pintype "power_in"))
      (node (ref "C5") (pin "1") (pinfunction "1_1") (pintype "power_in"))
      (node (ref "C6") (pin "1") (pinfunction "1_1") (pintype "power_in"))
      (node (ref "C7") (pin "1") (pinfunction "1_1") (pintype "power_in"))
      (node (ref "C8") (pin "1") (pinfunction "1_1") (pintype "power_in"))
      (node (ref "C9") (pin "1") (pinfunction "1_1") (pintype "power_in"))
      (node (ref "D1") (pin "23") (pinfunction "VSS_23") (pintype "passive"))
      (node (ref "D1") (pin "35") (pinfunction "VSS_35") (pintype "passive"))
      (node (ref "D1") (pin "47") (pinfunction "VSS_47") (pintype "passive"))
      (node (ref "D1") (pin "8") (pinfunction "VSSA/VREF-_8") (pintype "passive"))
      (node (ref "D2") (pin "4") (pinfunction "GND_4") (pintype "passive"))
      (node (ref "R18") (pin "1") (pinfunction "1_1") (pintype "passive"))
      (node (ref "R2") (pin "1") (pinfunction "1_1") (pintype "passive"))
      (node (ref "R22") (pin "1") (pinfunction "1_1") (pintype "passive"))
      (node (ref "R8") (pin "1") (pinfunction "1_1") (pintype "passive"))
      (node (ref "VD1") (pin "2") (pinfunction "C_2") (pintype "passive"))
      (node (ref "VD2") (pin "2") (pinfunction "C_2") (pintype "passive"))
      (node (ref "VT1") (pin "2") (pinfunction "S_2") (pintype "passive"))
      (node (ref "VT2") (pin "2") (pinfunction "S_2") (pintype "passive"))
      (node (ref "X1") (pin "16") (pinfunction "16_16") (pintype "passive"))
      (node (ref "X1") (pin "37") (pinfunction "37_37") (pintype "passive"))
      (node (ref "X1") (pin "5") (pinfunction "5_5") (pintype "passive"))
      (node (ref "X2") (pin "5") (pinfunction "5_5") (pintype "power_in"))
      (node (ref "X3") (pin "4") (pinfunction "4_4") (pintype "power_in"))
      (node (ref "X4") (pin "6") (pinfunction "6_6") (pintype "power_in"))
    )
    (net (code "24") (name "Net-(BF1--)") (class "Default")
      (node (ref "BF1") (pin "2") (pinfunction "-_2") (pintype "passive"))
      (node (ref "VD3") (pin "1") (pinfunction "1_1") (pintype "passive"))
      (node (ref "VT2") (pin "3") (pinfunction "D_3") (pintype "passive"))
    )
    (net (code "25") (name "Net-(D1-BOOT0)") (class "Default")
      (node (ref "D1") (pin "44") (pinfunction "BOOT0_44") (pintype "input"))
      (node (ref "R2") (pin "2") (pinfunction "2_2") (pintype "passive"))
    )
    (net (code "26") (name "Net-(D1-VCAP1)") (class "Default")
      (node (ref "C7") (pin "2") (pinfunction "2_2") (pintype "power_in"))
      (node (ref "D1") (pin "22") (pinfunction "VCAP1_22") (pintype "passive"))
    )
    (net (code "27") (name "Net-(D1-nRST)") (class "Default")
      (node (ref "C8") (pin "2") (pinfunction "2_2") (pintype "power_in"))
      (node (ref "D1") (pin "7") (pinfunction "nRST_7") (pintype "input"))
      (node (ref "R1") (pin "1") (pinfunction "1_1") (pintype "passive"))
    )
    (net (code "28") (name "Net-(D2-BST)") (class "Default")
      (node (ref "C14") (pin "1") (pinfunction "1_1") (pintype "power_in"))
      (node (ref "D2") (pin "6") (pinfunction "BST_6") (pintype "passive"))
    )
    (net (code "29") (name "Net-(D2-FB)") (class "Default")
      (node (ref "D2") (pin "1") (pinfunction "FB_1") (pintype "passive"))
      (node (ref "R16") (pin "2") (pinfunction "2_2") (pintype "passive"))
      (node (ref "R18") (pin "2") (pinfunction "2_2") (pintype "passive"))
    )
    (net (code "30") (name "Net-(D2-SW)") (class "Default")
      (node (ref "C14") (pin "2") (pinfunction "2_2") (pintype "power_in"))
      (node (ref "D2") (pin "5") (pinfunction "SW_5") (pintype "passive"))
      (node (ref "L1") (pin "2") (pinfunction "2_2") (pintype "passive"))
    )
    (net (code "31") (name "Net-(R3-Pad2)") (class "Default")
      (node (ref "R3") (pin "2") (pinfunction "2_2") (pintype "passive"))
      (node (ref "R4") (pin "2") (pinfunction "2_2") (pintype "passive"))
      (node (ref "X4") (pin "1") (pinfunction "1_1") (pintype "passive"))
    )
    (net (code "32") (name "Net-(R6-Pad1)") (class "Default")
      (node (ref "R6") (pin "1") (pinfunction "1_1") (pintype "passive"))
      (node (ref "X3") (pin "2") (pinfunction "2_2") (pintype "passive"))
    )
    (net (code "33") (name "Net-(R9-Pad1)") (class "Default")
      (node (ref "R9") (pin "1") (pinfunction "1_1") (pintype "passive"))
      (node (ref "X3") (pin "3") (pinfunction "3_3") (pintype "power_in"))
    )
    (net (code "34") (name "Net-(R10-Pad2)") (class "Default")
      (node (ref "R10") (pin "2") (pinfunction "2_2") (pintype "passive"))
      (node (ref "R7") (pin "2") (pinfunction "2_2") (pintype "passive"))
      (node (ref "X4") (pin "2") (pinfunction "2_2") (pintype "passive"))
    )
    (net (code "35") (name "Net-(R11-Pad2)") (class "Default")
      (node (ref "R11") (pin "2") (pinfunction "2_2") (pintype "passive"))
      (node (ref "R12") (pin "2") (pinfunction "2_2") (pintype "passive"))
      (node (ref "X4") (pin "3") (pinfunction "3_3") (pintype "power_in"))
    )
    (net (code "36") (name "Net-(R14-Pad2)") (class "Default")
      (node (ref "R14") (pin "2") (pinfunction "2_2") (pintype "passive"))
      (node (ref "R15") (pin "2") (pinfunction "2_2") (pintype "passive"))
      (node (ref "X4") (pin "4") (pinfunction "4_4") (pintype "power_in"))
    )
    (net (code "37") (name "Net-(R19-Pad2)") (class "Default")
      (node (ref "R19") (pin "2") (pinfunction "2_2") (pintype "passive"))
      (node (ref "R20") (pin "2") (pinfunction "2_2") (pintype "passive"))
      (node (ref "X4") (pin "5") (pinfunction "5_5") (pintype "power_in"))
    )
    (net (code "38") (name "Net-(VD1-A)") (class "Default")
      (node (ref "R13") (pin "1") (pinfunction "1_1") (pintype "passive"))
      (node (ref "VD1") (pin "1") (pinfunction "A_1") (pintype "passive"))
    )
    (net (code "39") (name "Net-(VD2-A)") (class "Default")
      (node (ref "R17") (pin "1") (pinfunction "1_1") (pintype "passive"))
      (node (ref "VD2") (pin "1") (pinfunction "A_1") (pintype "passive"))
    )
    (net (code "40") (name "Net-(VT1-D)") (class "Default")
      (node (ref "VT1") (pin "3") (pinfunction "D_3") (pintype "passive"))
      (node (ref "X1") (pin "34") (pinfunction "34_34") (pintype "passive"))
      (node (ref "X1") (pin "35") (pinfunction "35_35") (pintype "passive"))
      (node (ref "X1") (pin "36") (pinfunction "36_36") (pintype "passive"))
    )
    (net (code "41") (name "Net-(VT1-G)") (class "Default")
      (node (ref "R5") (pin "2") (pinfunction "2_2") (pintype "passive"))
      (node (ref "R8") (pin "2") (pinfunction "2_2") (pintype "passive"))
      (node (ref "VT1") (pin "1") (pinfunction "G_1") (pintype "passive"))
    )
    (net (code "42") (name "Net-(VT2-G)") (class "Default")
      (node (ref "R21") (pin "2") (pinfunction "2_2") (pintype "passive"))
      (node (ref "R22") (pin "2") (pinfunction "2_2") (pintype "passive"))
      (node (ref "VT2") (pin "1") (pinfunction "G_1") (pintype "passive"))
    )
    (net (code "43") (name "unconnected-(D1-PA0{slash}WKUP-Pad10)") (class "Default")
      (node (ref "D1") (pin "10") (pinfunction "PA0/WKUP_10") (pintype "bidirectional"))
    )
    (net (code "44") (name "unconnected-(D1-PA1-Pad11)") (class "Default")
      (node (ref "D1") (pin "11") (pinfunction "PA1_11") (pintype "bidirectional"))
    )
    (net (code "45") (name "unconnected-(D1-PA8-Pad29)") (class "Default")
      (node (ref "D1") (pin "29") (pinfunction "PA8_29") (pintype "bidirectional"))
    )
    (net (code "46") (name "unconnected-(D1-PA9-Pad30)") (class "Default")
      (node (ref "D1") (pin "30") (pinfunction "PA9_30") (pintype "bidirectional"))
    )
    (net (code "47") (name "unconnected-(D1-PA10-Pad31)") (class "Default")
      (node (ref "D1") (pin "31") (pinfunction "PA10_31") (pintype "bidirectional"))
    )
    (net (code "48") (name "unconnected-(D1-PA11-Pad32)") (class "Default")
      (node (ref "D1") (pin "32") (pinfunction "PA11_32") (pintype "bidirectional"))
    )
    (net (code "49") (name "unconnected-(D1-PA12-Pad33)") (class "Default")
      (node (ref "D1") (pin "33") (pinfunction "PA12_33") (pintype "bidirectional"))
    )
    (net (code "50") (name "unconnected-(D1-PA15-Pad38)") (class "Default")
      (node (ref "D1") (pin "38") (pinfunction "PA15_38") (pintype "bidirectional"))
    )
    (net (code "51") (name "unconnected-(D1-PB2-Pad20)") (class "Default")
      (node (ref "D1") (pin "20") (pinfunction "PB2_20") (pintype "bidirectional"))
    )
    (net (code "52") (name "unconnected-(D1-PB8-Pad45)") (class "Default")
      (node (ref "D1") (pin "45") (pinfunction "PB8_45") (pintype "bidirectional"))
    )
    (net (code "53") (name "unconnected-(D1-PB9-Pad46)") (class "Default")
      (node (ref "D1") (pin "46") (pinfunction "PB9_46") (pintype "bidirectional"))
    )
    (net (code "54") (name "unconnected-(D1-PB10-Pad21)") (class "Default")
      (node (ref "D1") (pin "21") (pinfunction "PB10_21") (pintype "bidirectional"))
    )
    (net (code "55") (name "unconnected-(D1-PB12-Pad25)") (class "Default")
      (node (ref "D1") (pin "25") (pinfunction "PB12_25") (pintype "bidirectional"))
    )
    (net (code "56") (name "unconnected-(D1-PB13-Pad26)") (class "Default")
      (node (ref "D1") (pin "26") (pinfunction "PB13_26") (pintype "bidirectional"))
    )
    (net (code "57") (name "unconnected-(D1-PB14-Pad27)") (class "Default")
      (node (ref "D1") (pin "27") (pinfunction "PB14_27") (pintype "bidirectional"))
    )
    (net (code "58") (name "unconnected-(D1-PB15-Pad28)") (class "Default")
      (node (ref "D1") (pin "28") (pinfunction "PB15_28") (pintype "bidirectional"))
    )
    (net (code "59") (name "unconnected-(X1-Pad1)") (class "Default")
      (node (ref "X1") (pin "1") (pinfunction "1_1") (pintype "passive"))
    )
    (net (code "60") (name "unconnected-(X1-Pad2)") (class "Default")
      (node (ref "X1") (pin "2") (pinfunction "2_2") (pintype "passive"))
    )
    (net (code "61") (name "unconnected-(X1-Pad3)") (class "Default")
      (node (ref "X1") (pin "3") (pinfunction "3_3") (pintype "passive"))
    )
    (net (code "62") (name "unconnected-(X1-Pad4)") (class "Default")
      (node (ref "X1") (pin "4") (pinfunction "4_4") (pintype "passive"))
    )
    (net (code "63") (name "unconnected-(X1-Pad8)") (class "Default")
      (node (ref "X1") (pin "8") (pinfunction "8_8") (pintype "passive"))
    )
    (net (code "64") (name "unconnected-(X1-Pad12)") (class "Default")
      (node (ref "X1") (pin "12") (pinfunction "12_12") (pintype "passive"))
    )
    (net (code "65") (name "unconnected-(X1-Pad17)") (class "Default")
      (node (ref "X1") (pin "17") (pinfunction "17_17") (pintype "passive"))
    )
    (net (code "66") (name "unconnected-(X1-Pad18)") (class "Default")
      (node (ref "X1") (pin "18") (pinfunction "18_18") (pintype "passive"))
    )
    (net (code "67") (name "unconnected-(X1-Pad19)") (class "Default")
      (node (ref "X1") (pin "19") (pinfunction "19_19") (pintype "passive"))
    )
    (net (code "68") (name "unconnected-(X1-Pad20)") (class "Default")
      (node (ref "X1") (pin "20") (pinfunction "20_20") (pintype "passive"))
    )
    (net (code "69") (name "unconnected-(X1-Pad21)") (class "Default")
      (node (ref "X1") (pin "21") (pinfunction "21_21") (pintype "passive"))
    )
    (net (code "70") (name "unconnected-(X1-Pad22)") (class "Default")
      (node (ref "X1") (pin "22") (pinfunction "22_22") (pintype "passive"))
    )
    (net (code "71") (name "unconnected-(X1-Pad23)") (class "Default")
      (node (ref "X1") (pin "23") (pinfunction "23_23") (pintype "passive"))
    )
    (net (code "72") (name "unconnected-(X1-Pad24)") (class "Default")
      (node (ref "X1") (pin "24") (pinfunction "24_24") (pintype "passive"))
    )
    (net (code "73") (name "unconnected-(X1-Pad25)") (class "Default")
      (node (ref "X1") (pin "25") (pinfunction "25_25") (pintype "passive"))
    )
    (net (code "74") (name "unconnected-(X1-Pad26)") (class "Default")
      (node (ref "X1") (pin "26") (pinfunction "26_26") (pintype "passive"))
    )
    (net (code "75") (name "unconnected-(X1-Pad27)") (class "Default")
      (node (ref "X1") (pin "27") (pinfunction "27_27") (pintype "passive"))
    )
    (net (code "76") (name "unconnected-(X1-Pad28)") (class "Default")
      (node (ref "X1") (pin "28") (pinfunction "28_28") (pintype "passive"))
    )
    (net (code "77") (name "unconnected-(X1-Pad29)") (class "Default")
      (node (ref "X1") (pin "29") (pinfunction "29_29") (pintype "passive"))
    )
    (net (code "78") (name "unconnected-(X1-Pad30)") (class "Default")
      (node (ref "X1") (pin "30") (pinfunction "30_30") (pintype "passive"))
    )
    (net (code "79") (name "unconnected-(X1-Pad31)") (class "Default")
      (node (ref "X1") (pin "31") (pinfunction "31_31") (pintype "passive"))
    )
    (net (code "80") (name "unconnected-(X1-Pad32)") (class "Default")
      (node (ref "X1") (pin "32") (pinfunction "32_32") (pintype "passive"))
    )
  )
)
